# SDRAM.net
KiCad netlist of a schematic drawn in Altium Designer
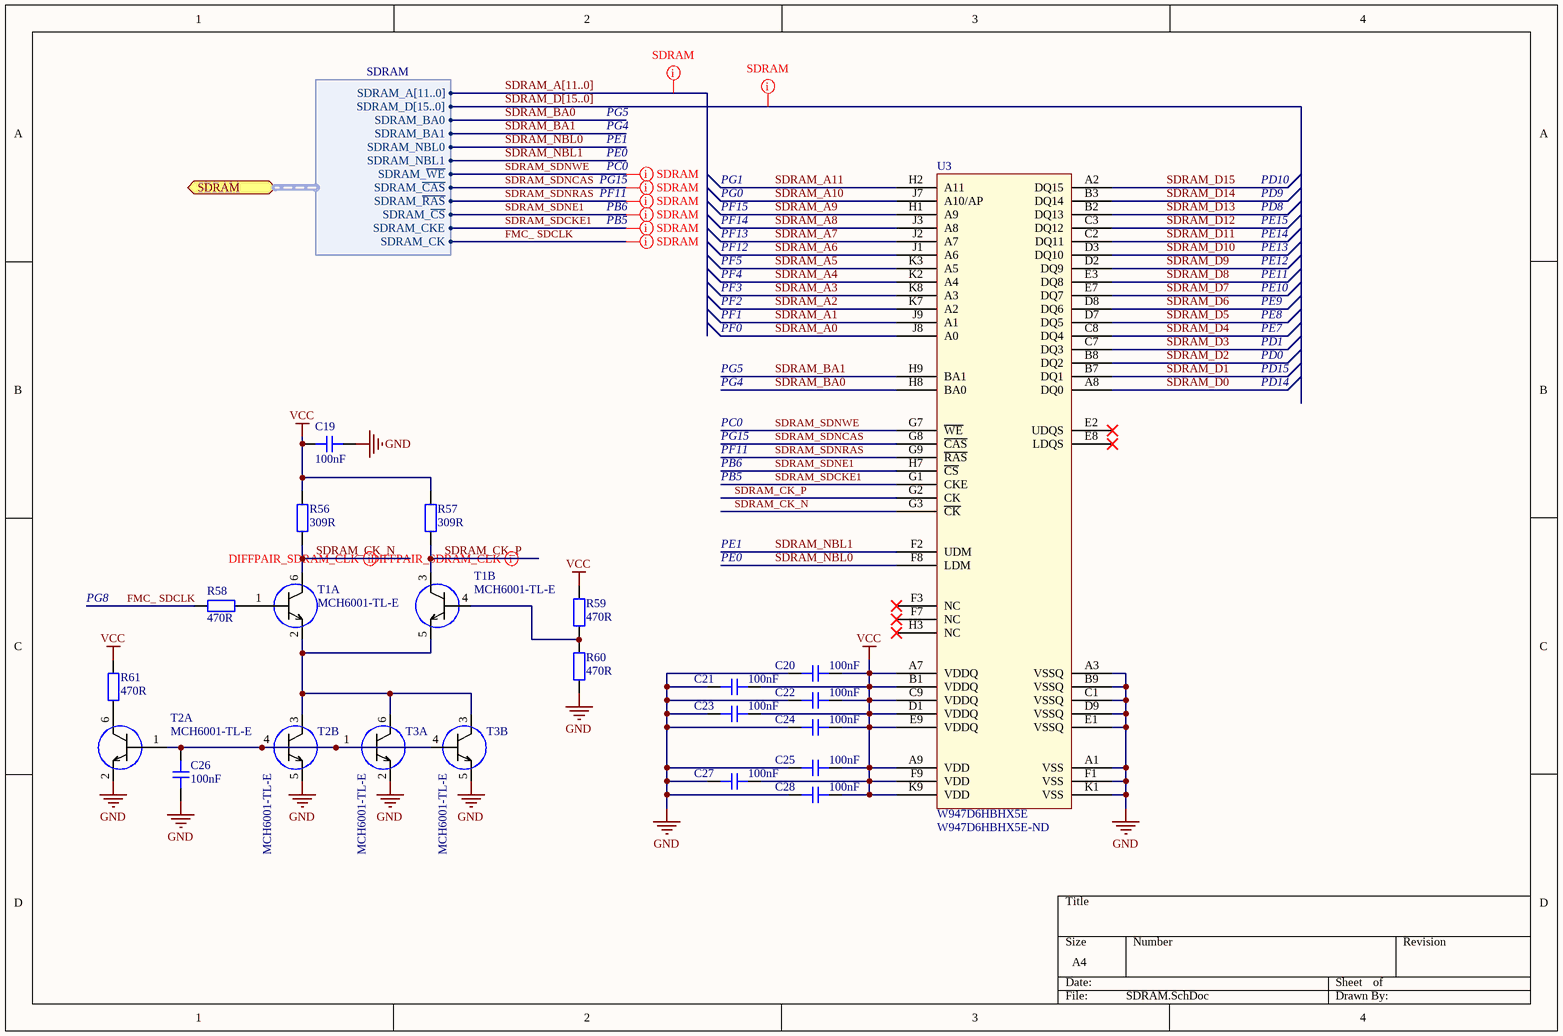
[diagram p0: SDRAM.SchDoc]

(export (version "E")
  (design (tool "Eeschema 10.0.6"))
  (components
    (comp (ref "C19")
      (value "100nF")
      (footprint "Capacitor-0603")
      (fields (field (name "Comment") "C-100nF-0603"))
      (libsource (lib "Components") (part "C-100nF-0603"))
    )
    (comp (ref "C20")
      (value "100nF")
      (footprint "Capacitor-0603")
      (fields (field (name "Comment") "C-100nF-0603"))
      (libsource (lib "Components") (part "C-100nF-0603"))
    )
    (comp (ref "C21")
      (value "100nF")
      (footprint "Capacitor-0603")
      (fields (field (name "Comment") "C-100nF-0603"))
      (libsource (lib "Components") (part "C-100nF-0603"))
    )
    (comp (ref "C22")
      (value "100nF")
      (footprint "Capacitor-0603")
      (fields (field (name "Comment") "C-100nF-0603"))
      (libsource (lib "Components") (part "C-100nF-0603"))
    )
    (comp (ref "C23")
      (value "100nF")
      (footprint "Capacitor-0603")
      (fields (field (name "Comment") "C-100nF-0603"))
      (libsource (lib "Components") (part "C-100nF-0603"))
    )
    (comp (ref "C24")
      (value "100nF")
      (footprint "Capacitor-0603")
      (fields (field (name "Comment") "C-100nF-0603"))
      (libsource (lib "Components") (part "C-100nF-0603"))
    )
    (comp (ref "C25")
      (value "100nF")
      (footprint "Capacitor-0603")
      (fields (field (name "Comment") "C-100nF-0603"))
      (libsource (lib "Components") (part "C-100nF-0603"))
    )
    (comp (ref "C26")
      (value "100nF")
      (footprint "Capacitor-0603")
      (fields (field (name "Comment") "C-100nF-0603"))
      (libsource (lib "Components") (part "C-100nF-0603"))
    )
    (comp (ref "C27")
      (value "100nF")
      (footprint "Capacitor-0603")
      (fields (field (name "Comment") "C-100nF-0603"))
      (libsource (lib "Components") (part "C-100nF-0603"))
    )
    (comp (ref "C28")
      (value "100nF")
      (footprint "Capacitor-0603")
      (fields (field (name "Comment") "C-100nF-0603"))
      (libsource (lib "Components") (part "C-100nF-0603"))
    )
    (comp (ref "R56")
      (value "309R")
      (footprint "Resistor-0603")
      (fields (field (name "Comment") "R-309R-0603"))
      (libsource (lib "Components") (part "R-309R-0603"))
    )
    (comp (ref "R57")
      (value "309R")
      (footprint "Resistor-0603")
      (fields (field (name "Comment") "R-309R-0603"))
      (libsource (lib "Components") (part "R-309R-0603"))
    )
    (comp (ref "R58")
      (value "470R")
      (footprint "Resistor-0603")
      (fields (field (name "Comment") "R-470R-0603"))
      (libsource (lib "Components") (part "R-470R-0603"))
    )
    (comp (ref "R59")
      (value "470R")
      (footprint "Resistor-0603")
      (fields (field (name "Comment") "R-470R-0603"))
      (libsource (lib "Components") (part "R-470R-0603"))
    )
    (comp (ref "R60")
      (value "470R")
      (footprint "Resistor-0603")
      (fields (field (name "Comment") "R-470R-0603"))
      (libsource (lib "Components") (part "R-470R-0603"))
    )
    (comp (ref "R61")
      (value "470R")
      (footprint "Resistor-0603")
      (fields (field (name "Comment") "R-470R-0603"))
      (libsource (lib "Components") (part "R-470R-0603"))
    )
    (comp (ref "T1")
      (value "MCH6001-TL-E")
      (footprint "MCH6001-TL-E")
      (libsource (lib "Components") (part "MCH6001-TL-E"))
    )
    (comp (ref "T2")
      (value "MCH6001-TL-E")
      (footprint "MCH6001-TL-E")
      (libsource (lib "Components") (part "MCH6001-TL-E"))
    )
    (comp (ref "T3")
      (value "MCH6001-TL-E")
      (footprint "MCH6001-TL-E")
      (libsource (lib "Components") (part "MCH6001-TL-E"))
    )
    (comp (ref "U3")
      (value "W947D6HBHX5E")
      (footprint "W947D6HBHX5E")
      (fields (field (name "SUPPLIER PART NUMBER 1") "W947D6HBHX5E-ND"))
      (libsource (lib "Components") (part "W947D6HBHX5E"))
    )
  )
  (nets
    (net (code "2") (name "/FMC_ SDCLK") (class "Default")
      (node (ref "R58") (pin "2") (pinfunction "2_2") (pintype "passive"))
    )
    (net (code "3") (name "/SDRAM_A0") (class "Default")
      (node (ref "U3") (pin "J8") (pinfunction "A0_J8") (pintype "passive"))
    )
    (net (code "4") (name "/SDRAM_A1") (class "Default")
      (node (ref "U3") (pin "J9") (pinfunction "A1_J9") (pintype "passive"))
    )
    (net (code "5") (name "/SDRAM_A2") (class "Default")
      (node (ref "U3") (pin "K7") (pinfunction "A2_K7") (pintype "passive"))
    )
    (net (code "6") (name "/SDRAM_A3") (class "Default")
      (node (ref "U3") (pin "K8") (pinfunction "A3_K8") (pintype "passive"))
    )
    (net (code "7") (name "/SDRAM_A4") (class "Default")
      (node (ref "U3") (pin "K2") (pinfunction "A4_K2") (pintype "passive"))
    )
    (net (code "8") (name "/SDRAM_A5") (class "Default")
      (node (ref "U3") (pin "K3") (pinfunction "A5_K3") (pintype "passive"))
    )
    (net (code "9") (name "/SDRAM_A6") (class "Default")
      (node (ref "U3") (pin "J1") (pinfunction "A6_J1") (pintype "passive"))
    )
    (net (code "10") (name "/SDRAM_A7") (class "Default")
      (node (ref "U3") (pin "J2") (pinfunction "A7_J2") (pintype "passive"))
    )
    (net (code "11") (name "/SDRAM_A8") (class "Default")
      (node (ref "U3") (pin "J3") (pinfunction "A8_J3") (pintype "passive"))
    )
    (net (code "12") (name "/SDRAM_A9") (class "Default")
      (node (ref "U3") (pin "H1") (pinfunction "A9_H1") (pintype "passive"))
    )
    (net (code "13") (name "/SDRAM_A10") (class "Default")
      (node (ref "U3") (pin "J7") (pinfunction "A10/AP_J7") (pintype "passive"))
    )
    (net (code "14") (name "/SDRAM_A11") (class "Default")
      (node (ref "U3") (pin "H2") (pinfunction "A11_H2") (pintype "passive"))
    )
    (net (code "16") (name "/SDRAM_BA0") (class "Default")
      (node (ref "U3") (pin "H8") (pinfunction "BA0_H8") (pintype "passive"))
    )
    (net (code "17") (name "/SDRAM_BA1") (class "Default")
      (node (ref "U3") (pin "H9") (pinfunction "BA1_H9") (pintype "passive"))
    )
    (net (code "18") (name "/SDRAM_CK_N") (class "Default")
      (node (ref "R56") (pin "1") (pinfunction "1_1") (pintype "passive"))
      (node (ref "T1") (pin "6") (pinfunction "C1_6") (pintype "passive"))
      (node (ref "U3") (pin "G3") (pinfunction "~{CK}_G3") (pintype "passive"))
    )
    (net (code "19") (name "/SDRAM_CK_P") (class "Default")
      (node (ref "R57") (pin "1") (pinfunction "1_1") (pintype "passive"))
      (node (ref "T1") (pin "3") (pinfunction "C2_3") (pintype "passive"))
      (node (ref "U3") (pin "G2") (pinfunction "CK_G2") (pintype "passive"))
    )
    (net (code "20") (name "/SDRAM_D0") (class "Default")
      (node (ref "U3") (pin "A8") (pinfunction "DQ0_A8") (pintype "passive"))
    )
    (net (code "21") (name "/SDRAM_D1") (class "Default")
      (node (ref "U3") (pin "B7") (pinfunction "DQ1_B7") (pintype "passive"))
    )
    (net (code "22") (name "/SDRAM_D2") (class "Default")
      (node (ref "U3") (pin "B8") (pinfunction "DQ2_B8") (pintype "passive"))
    )
    (net (code "23") (name "/SDRAM_D3") (class "Default")
      (node (ref "U3") (pin "C7") (pinfunction "DQ3_C7") (pintype "passive"))
    )
    (net (code "24") (name "/SDRAM_D4") (class "Default")
      (node (ref "U3") (pin "C8") (pinfunction "DQ4_C8") (pintype "passive"))
    )
    (net (code "25") (name "/SDRAM_D5") (class "Default")
      (node (ref "U3") (pin "D7") (pinfunction "DQ5_D7") (pintype "passive"))
    )
    (net (code "26") (name "/SDRAM_D6") (class "Default")
      (node (ref "U3") (pin "D8") (pinfunction "DQ6_D8") (pintype "passive"))
    )
    (net (code "27") (name "/SDRAM_D7") (class "Default")
      (node (ref "U3") (pin "E7") (pinfunction "DQ7_E7") (pintype "passive"))
    )
    (net (code "28") (name "/SDRAM_D8") (class "Default")
      (node (ref "U3") (pin "E3") (pinfunction "DQ8_E3") (pintype "passive"))
    )
    (net (code "29") (name "/SDRAM_D9") (class "Default")
      (node (ref "U3") (pin "D2") (pinfunction "DQ9_D2") (pintype "passive"))
    )
    (net (code "30") (name "/SDRAM_D10") (class "Default")
      (node (ref "U3") (pin "D3") (pinfunction "DQ10_D3") (pintype "passive"))
    )
    (net (code "31") (name "/SDRAM_D11") (class "Default")
      (node (ref "U3") (pin "C2") (pinfunction "DQ11_C2") (pintype "passive"))
    )
    (net (code "32") (name "/SDRAM_D12") (class "Default")
      (node (ref "U3") (pin "C3") (pinfunction "DQ12_C3") (pintype "passive"))
    )
    (net (code "33") (name "/SDRAM_D13") (class "Default")
      (node (ref "U3") (pin "B2") (pinfunction "DQ13_B2") (pintype "passive"))
    )
    (net (code "34") (name "/SDRAM_D14") (class "Default")
      (node (ref "U3") (pin "B3") (pinfunction "DQ14_B3") (pintype "passive"))
    )
    (net (code "35") (name "/SDRAM_D15") (class "Default")
      (node (ref "U3") (pin "A2") (pinfunction "DQ15_A2") (pintype "passive"))
    )
    (net (code "37") (name "/SDRAM_NBL0") (class "Default")
      (node (ref "U3") (pin "F8") (pinfunction "LDM_F8") (pintype "passive"))
    )
    (net (code "38") (name "/SDRAM_NBL1") (class "Default")
      (node (ref "U3") (pin "F2") (pinfunction "UDM_F2") (pintype "passive"))
    )
    (net (code "39") (name "/SDRAM_SDCKE1") (class "Default")
      (node (ref "U3") (pin "G1") (pinfunction "CKE_G1") (pintype "passive"))
    )
    (net (code "40") (name "/SDRAM_SDNCAS") (class "Default")
      (node (ref "U3") (pin "G8") (pinfunction "~{CAS}_G8") (pintype "passive"))
    )
    (net (code "41") (name "/SDRAM_SDNE1") (class "Default")
      (node (ref "U3") (pin "H7") (pinfunction "~{CS}_H7") (pintype "passive"))
    )
    (net (code "42") (name "/SDRAM_SDNRAS") (class "Default")
      (node (ref "U3") (pin "G9") (pinfunction "~{RAS}_G9") (pintype "passive"))
    )
    (net (code "43") (name "/SDRAM_SDNWE") (class "Default")
      (node (ref "U3") (pin "G7") (pinfunction "~{WE}_G7") (pintype "passive"))
    )
    (net (code "45") (name "GND") (class "Default")
      (node (ref "C19") (pin "1") (pinfunction "1_1") (pintype "passive"))
      (node (ref "C20") (pin "1") (pinfunction "1_1") (pintype "passive"))
      (node (ref "C21") (pin "1") (pinfunction "1_1") (pintype "passive"))
      (node (ref "C22") (pin "1") (pinfunction "1_1") (pintype "passive"))
      (node (ref "C23") (pin "1") (pinfunction "1_1") (pintype "passive"))
      (node (ref "C24") (pin "1") (pinfunction "1_1") (pintype "passive"))
      (node (ref "C25") (pin "1") (pinfunction "1_1") (pintype "passive"))
      (node (ref "C26") (pin "1") (pinfunction "1_1") (pintype "passive"))
      (node (ref "C27") (pin "1") (pinfunction "1_1") (pintype "passive"))
      (node (ref "C28") (pin "1") (pinfunction "1_1") (pintype "passive"))
      (node (ref "R60") (pin "2") (pinfunction "2_2") (pintype "passive"))
      (node (ref "T2") (pin "2") (pinfunction "E1_2") (pintype "passive"))
      (node (ref "T2") (pin "5") (pinfunction "E2_5") (pintype "passive"))
      (node (ref "T3") (pin "2") (pinfunction "E1_2") (pintype "passive"))
      (node (ref "T3") (pin "5") (pinfunction "E2_5") (pintype "passive"))
      (node (ref "U3") (pin "A1") (pinfunction "VSS_A1") (pintype "passive"))
      (node (ref "U3") (pin "A3") (pinfunction "VSSQ_A3") (pintype "passive"))
      (node (ref "U3") (pin "B9") (pinfunction "VSSQ_B9") (pintype "passive"))
      (node (ref "U3") (pin "C1") (pinfunction "VSSQ_C1") (pintype "passive"))
      (node (ref "U3") (pin "D9") (pinfunction "VSSQ_D9") (pintype "passive"))
      (node (ref "U3") (pin "E1") (pinfunction "VSSQ_E1") (pintype "passive"))
      (node (ref "U3") (pin "F1") (pinfunction "VSS_F1") (pintype "passive"))
      (node (ref "U3") (pin "K1") (pinfunction "VSS_K1") (pintype "passive"))
    )
    (net (code "46") (name "Net-(T1A-B1)") (class "Default")
      (node (ref "R58") (pin "1") (pinfunction "1_1") (pintype "passive"))
      (node (ref "T1") (pin "1") (pinfunction "B1_1") (pintype "passive"))
    )
    (net (code "47") (name "Net-(T1A-E1)") (class "Default")
      (node (ref "T1") (pin "2") (pinfunction "E1_2") (pintype "passive"))
      (node (ref "T1") (pin "5") (pinfunction "E2_5") (pintype "passive"))
      (node (ref "T2") (pin "3") (pinfunction "C2_3") (pintype "passive"))
      (node (ref "T3") (pin "3") (pinfunction "C2_3") (pintype "passive"))
      (node (ref "T3") (pin "6") (pinfunction "C1_6") (pintype "passive"))
    )
    (net (code "48") (name "Net-(T1B-B2)") (class "Default")
      (node (ref "R59") (pin "2") (pinfunction "2_2") (pintype "passive"))
      (node (ref "R60") (pin "1") (pinfunction "1_1") (pintype "passive"))
      (node (ref "T1") (pin "4") (pinfunction "B2_4") (pintype "passive"))
    )
    (net (code "49") (name "Net-(T2A-B1)") (class "Default")
      (node (ref "C26") (pin "2") (pinfunction "2_2") (pintype "passive"))
      (node (ref "T2") (pin "1") (pinfunction "B1_1") (pintype "passive"))
      (node (ref "T2") (pin "4") (pinfunction "B2_4") (pintype "passive"))
      (node (ref "T3") (pin "1") (pinfunction "B1_1") (pintype "passive"))
      (node (ref "T3") (pin "4") (pinfunction "B2_4") (pintype "passive"))
    )
    (net (code "50") (name "Net-(T2A-C1)") (class "Default")
      (node (ref "R61") (pin "1") (pinfunction "1_1") (pintype "passive"))
      (node (ref "T2") (pin "6") (pinfunction "C1_6") (pintype "passive"))
    )
    (net (code "51") (name "VCC") (class "Default")
      (node (ref "C19") (pin "2") (pinfunction "2_2") (pintype "passive"))
      (node (ref "C20") (pin "2") (pinfunction "2_2") (pintype "passive"))
      (node (ref "C21") (pin "2") (pinfunction "2_2") (pintype "passive"))
      (node (ref "C22") (pin "2") (pinfunction "2_2") (pintype "passive"))
      (node (ref "C23") (pin "2") (pinfunction "2_2") (pintype "passive"))
      (node (ref "C24") (pin "2") (pinfunction "2_2") (pintype "passive"))
      (node (ref "C25") (pin "2") (pinfunction "2_2") (pintype "passive"))
      (node (ref "C27") (pin "2") (pinfunction "2_2") (pintype "passive"))
      (node (ref "C28") (pin "2") (pinfunction "2_2") (pintype "passive"))
      (node (ref "R56") (pin "2") (pinfunction "2_2") (pintype "passive"))
      (node (ref "R57") (pin "2") (pinfunction "2_2") (pintype "passive"))
      (node (ref "R59") (pin "1") (pinfunction "1_1") (pintype "passive"))
      (node (ref "R61") (pin "2") (pinfunction "2_2") (pintype "passive"))
      (node (ref "U3") (pin "A7") (pinfunction "VDDQ_A7") (pintype "passive"))
      (node (ref "U3") (pin "A9") (pinfunction "VDD_A9") (pintype "passive"))
      (node (ref "U3") (pin "B1") (pinfunction "VDDQ_B1") (pintype "passive"))
      (node (ref "U3") (pin "C9") (pinfunction "VDDQ_C9") (pintype "passive"))
      (node (ref "U3") (pin "D1") (pinfunction "VDDQ_D1") (pintype "passive"))
      (node (ref "U3") (pin "E9") (pinfunction "VDDQ_E9") (pintype "passive"))
      (node (ref "U3") (pin "F9") (pinfunction "VDD_F9") (pintype "passive"))
      (node (ref "U3") (pin "K9") (pinfunction "VDD_K9") (pintype "passive"))
    )
    (net (code "52") (name "unconnected-(U3-LDQS-PadE8)") (class "Default")
      (node (ref "U3") (pin "E8") (pinfunction "LDQS_E8") (pintype "passive+no_connect"))
    )
    (net (code "53") (name "unconnected-(U3-NC-PadF3)") (class "Default")
      (node (ref "U3") (pin "F3") (pinfunction "NC_F3") (pintype "passive+no_connect"))
    )
    (net (code "54") (name "unconnected-(U3-NC-PadF7)") (class "Default")
      (node (ref "U3") (pin "F7") (pinfunction "NC_F7") (pintype "passive+no_connect"))
    )
    (net (code "55") (name "unconnected-(U3-NC-PadH3)") (class "Default")
      (node (ref "U3") (pin "H3") (pinfunction "NC_H3") (pintype "passive+no_connect"))
    )
    (net (code "56") (name "unconnected-(U3-UDQS-PadE2)") (class "Default")
      (node (ref "U3") (pin "E2") (pinfunction "UDQS_E2") (pintype "passive+no_connect"))
    )
  )
)
